# untitled.net
KiCad netlist of a schematic drawn in EAGLE
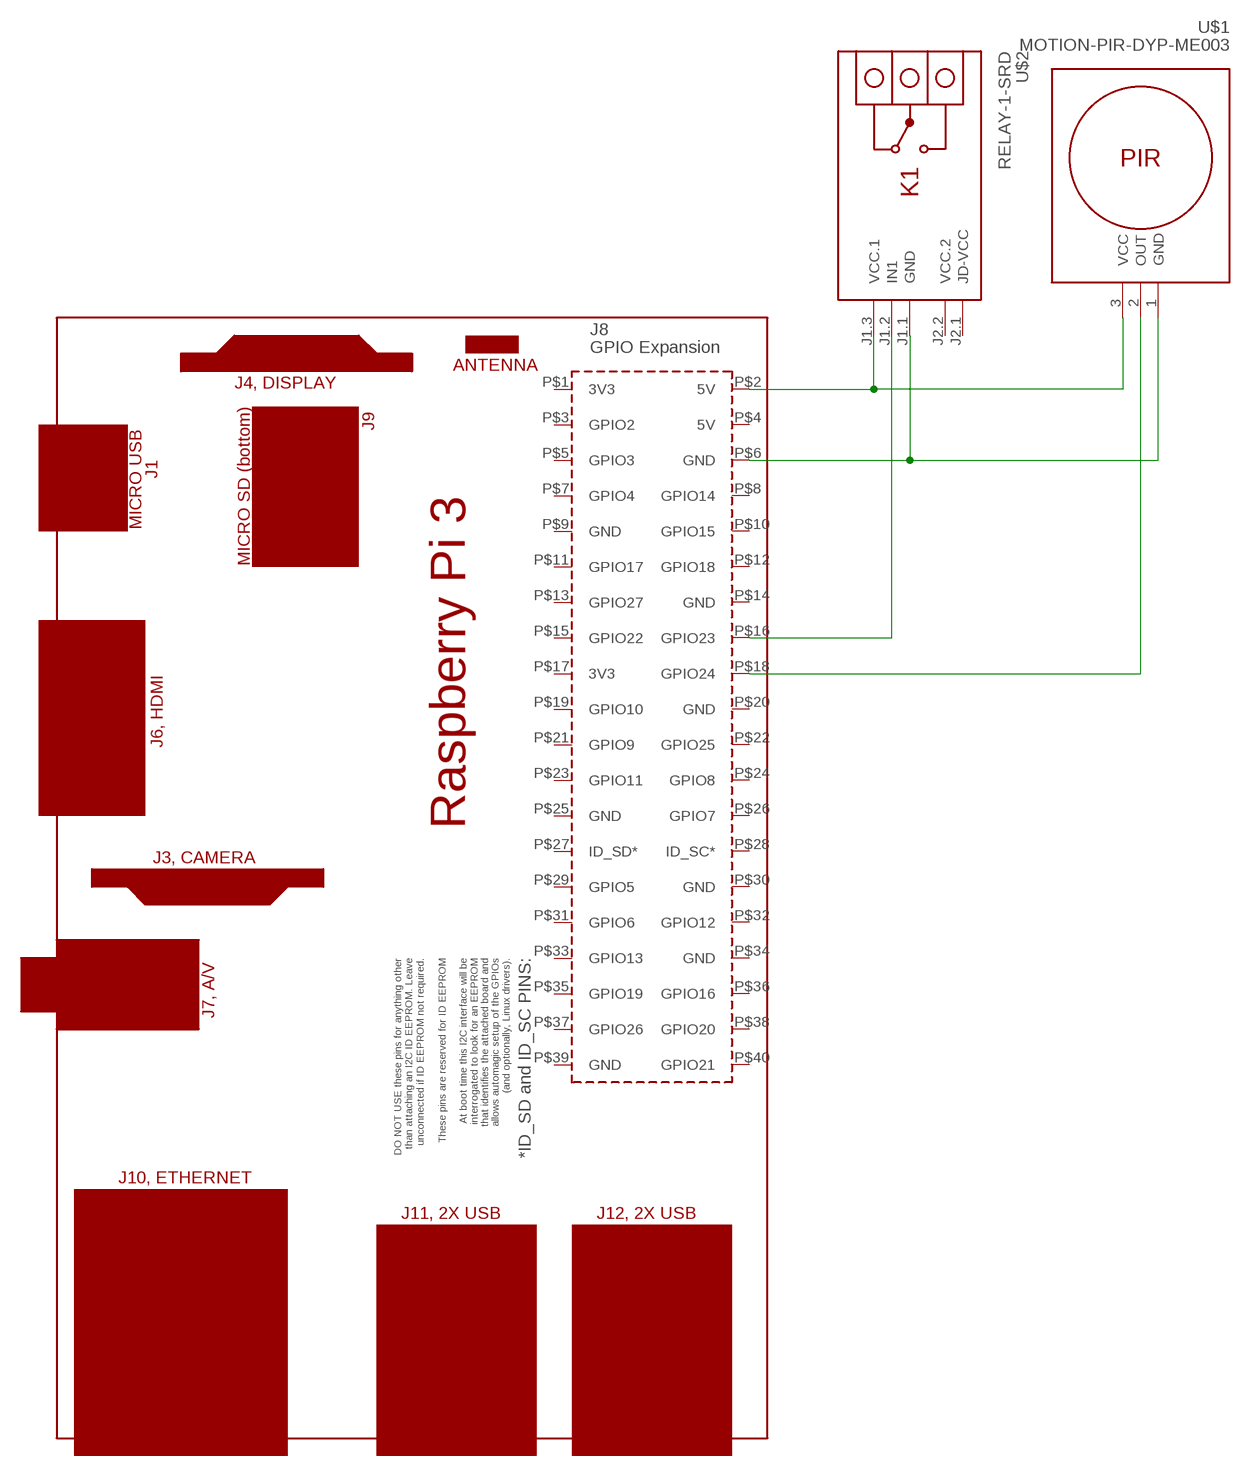
[diagram p0: schematic, sheet 1]

(export (version "E")
  (design (tool "Eeschema 10.0.6"))
  (components
    (comp (ref "PCB1")
      (value "RPI3RPI3")
      (footprint "eagle-import:RPI3")
      (libsource (lib "eagle-import") (part "RPI3RPI3"))
    )
    (comp (ref "U$1")
      (value "MOTION-PIR-DYP-ME003")
      (footprint "eagle-import:MOTION-PIR-DYP-ME003")
      (libsource (lib "eagle-import") (part "MOTION-PIR-DYP-ME003"))
    )
    (comp (ref "U$2")
      (value "RELAY-1-SRD")
      (footprint "eagle-import:RELAY-1-SRD")
      (libsource (lib "eagle-import") (part "RELAY-1-SRD"))
    )
  )
  (nets
    (net (code "1") (name "/VCC.2") (class "Default")
      (node (ref "U$2") (pin "J2.2") (pinfunction "VCC.2_J2.2") (pintype "power_in"))
    )
    (net (code "2") (name "Net-(PCB1-GPIO23)") (class "Default")
      (node (ref "PCB1") (pin "P$16") (pinfunction "GPIO23_P$16") (pintype "bidirectional"))
      (node (ref "U$2") (pin "J1.2") (pinfunction "IN1_J1.2") (pintype "bidirectional"))
    )
    (net (code "3") (name "Net-(PCB1-GPIO24)") (class "Default")
      (node (ref "PCB1") (pin "P$18") (pinfunction "GPIO24_P$18") (pintype "bidirectional"))
      (node (ref "U$1") (pin "2") (pinfunction "OUT_2") (pintype "output"))
    )
    (net (code "4") (name "Net-(U$1-GND)") (class "Default")
      (node (ref "PCB1") (pin "P$6") (pinfunction "GND_P$6") (pintype "bidirectional"))
      (node (ref "U$1") (pin "1") (pinfunction "GND_1") (pintype "power_in"))
      (node (ref "U$2") (pin "J1.1") (pinfunction "GND_J1.1") (pintype "power_in"))
    )
    (net (code "5") (name "Net-(U$1-VCC)") (class "Default")
      (node (ref "PCB1") (pin "P$2") (pinfunction "5V_P$2") (pintype "bidirectional"))
      (node (ref "U$1") (pin "3") (pinfunction "VCC_3") (pintype "power_in"))
      (node (ref "U$2") (pin "J1.3") (pinfunction "VCC.1_J1.3") (pintype "power_in"))
    )
    (net (code "6") (name "unconnected-(PCB1-3V3-PadP$1)") (class "Default")
      (node (ref "PCB1") (pin "P$1") (pinfunction "3V3_P$1") (pintype "bidirectional"))
    )
    (net (code "7") (name "unconnected-(PCB1-3V3-PadP$17)") (class "Default")
      (node (ref "PCB1") (pin "P$17") (pinfunction "3V3_P$17") (pintype "bidirectional"))
    )
    (net (code "8") (name "unconnected-(PCB1-5V-PadP$4)") (class "Default")
      (node (ref "PCB1") (pin "P$4") (pinfunction "5V_P$4") (pintype "bidirectional"))
    )
    (net (code "9") (name "unconnected-(PCB1-GND-PadP$9)") (class "Default")
      (node (ref "PCB1") (pin "P$9") (pinfunction "GND_P$9") (pintype "bidirectional"))
    )
    (net (code "10") (name "unconnected-(PCB1-GND-PadP$14)") (class "Default")
      (node (ref "PCB1") (pin "P$14") (pinfunction "GND_P$14") (pintype "bidirectional"))
    )
    (net (code "11") (name "unconnected-(PCB1-GND-PadP$20)") (class "Default")
      (node (ref "PCB1") (pin "P$20") (pinfunction "GND_P$20") (pintype "bidirectional"))
    )
    (net (code "12") (name "unconnected-(PCB1-GND-PadP$25)") (class "Default")
      (node (ref "PCB1") (pin "P$25") (pinfunction "GND_P$25") (pintype "bidirectional"))
    )
    (net (code "13") (name "unconnected-(PCB1-GND-PadP$30)") (class "Default")
      (node (ref "PCB1") (pin "P$30") (pinfunction "GND_P$30") (pintype "bidirectional"))
    )
    (net (code "14") (name "unconnected-(PCB1-GND-PadP$34)") (class "Default")
      (node (ref "PCB1") (pin "P$34") (pinfunction "GND_P$34") (pintype "bidirectional"))
    )
    (net (code "15") (name "unconnected-(PCB1-GND-PadP$39)") (class "Default")
      (node (ref "PCB1") (pin "P$39") (pinfunction "GND_P$39") (pintype "bidirectional"))
    )
    (net (code "16") (name "unconnected-(PCB1-GPIO2-PadP$3)") (class "Default")
      (node (ref "PCB1") (pin "P$3") (pinfunction "GPIO2_P$3") (pintype "bidirectional"))
    )
    (net (code "17") (name "unconnected-(PCB1-GPIO3-PadP$5)") (class "Default")
      (node (ref "PCB1") (pin "P$5") (pinfunction "GPIO3_P$5") (pintype "bidirectional"))
    )
    (net (code "18") (name "unconnected-(PCB1-GPIO4-PadP$7)") (class "Default")
      (node (ref "PCB1") (pin "P$7") (pinfunction "GPIO4_P$7") (pintype "bidirectional"))
    )
    (net (code "19") (name "unconnected-(PCB1-GPIO5-PadP$29)") (class "Default")
      (node (ref "PCB1") (pin "P$29") (pinfunction "GPIO5_P$29") (pintype "bidirectional"))
    )
    (net (code "20") (name "unconnected-(PCB1-GPIO6-PadP$31)") (class "Default")
      (node (ref "PCB1") (pin "P$31") (pinfunction "GPIO6_P$31") (pintype "bidirectional"))
    )
    (net (code "21") (name "unconnected-(PCB1-GPIO7-PadP$26)") (class "Default")
      (node (ref "PCB1") (pin "P$26") (pinfunction "GPIO7_P$26") (pintype "bidirectional"))
    )
    (net (code "22") (name "unconnected-(PCB1-GPIO8-PadP$24)") (class "Default")
      (node (ref "PCB1") (pin "P$24") (pinfunction "GPIO8_P$24") (pintype "bidirectional"))
    )
    (net (code "23") (name "unconnected-(PCB1-GPIO9-PadP$21)") (class "Default")
      (node (ref "PCB1") (pin "P$21") (pinfunction "GPIO9_P$21") (pintype "bidirectional"))
    )
    (net (code "24") (name "unconnected-(PCB1-GPIO10-PadP$19)") (class "Default")
      (node (ref "PCB1") (pin "P$19") (pinfunction "GPIO10_P$19") (pintype "bidirectional"))
    )
    (net (code "25") (name "unconnected-(PCB1-GPIO11-PadP$23)") (class "Default")
      (node (ref "PCB1") (pin "P$23") (pinfunction "GPIO11_P$23") (pintype "bidirectional"))
    )
    (net (code "26") (name "unconnected-(PCB1-GPIO12-PadP$32)") (class "Default")
      (node (ref "PCB1") (pin "P$32") (pinfunction "GPIO12_P$32") (pintype "bidirectional"))
    )
    (net (code "27") (name "unconnected-(PCB1-GPIO13-PadP$33)") (class "Default")
      (node (ref "PCB1") (pin "P$33") (pinfunction "GPIO13_P$33") (pintype "bidirectional"))
    )
    (net (code "28") (name "unconnected-(PCB1-GPIO14-PadP$8)") (class "Default")
      (node (ref "PCB1") (pin "P$8") (pinfunction "GPIO14_P$8") (pintype "bidirectional"))
    )
    (net (code "29") (name "unconnected-(PCB1-GPIO15-PadP$10)") (class "Default")
      (node (ref "PCB1") (pin "P$10") (pinfunction "GPIO15_P$10") (pintype "bidirectional"))
    )
    (net (code "30") (name "unconnected-(PCB1-GPIO16-PadP$36)") (class "Default")
      (node (ref "PCB1") (pin "P$36") (pinfunction "GPIO16_P$36") (pintype "bidirectional"))
    )
    (net (code "31") (name "unconnected-(PCB1-GPIO17-PadP$11)") (class "Default")
      (node (ref "PCB1") (pin "P$11") (pinfunction "GPIO17_P$11") (pintype "bidirectional"))
    )
    (net (code "32") (name "unconnected-(PCB1-GPIO18-PadP$12)") (class "Default")
      (node (ref "PCB1") (pin "P$12") (pinfunction "GPIO18_P$12") (pintype "bidirectional"))
    )
    (net (code "33") (name "unconnected-(PCB1-GPIO19-PadP$35)") (class "Default")
      (node (ref "PCB1") (pin "P$35") (pinfunction "GPIO19_P$35") (pintype "bidirectional"))
    )
    (net (code "34") (name "unconnected-(PCB1-GPIO20-PadP$38)") (class "Default")
      (node (ref "PCB1") (pin "P$38") (pinfunction "GPIO20_P$38") (pintype "bidirectional"))
    )
    (net (code "35") (name "unconnected-(PCB1-GPIO21-PadP$40)") (class "Default")
      (node (ref "PCB1") (pin "P$40") (pinfunction "GPIO21_P$40") (pintype "bidirectional"))
    )
    (net (code "36") (name "unconnected-(PCB1-GPIO22-PadP$15)") (class "Default")
      (node (ref "PCB1") (pin "P$15") (pinfunction "GPIO22_P$15") (pintype "bidirectional"))
    )
    (net (code "37") (name "unconnected-(PCB1-GPIO25-PadP$22)") (class "Default")
      (node (ref "PCB1") (pin "P$22") (pinfunction "GPIO25_P$22") (pintype "bidirectional"))
    )
    (net (code "38") (name "unconnected-(PCB1-GPIO26-PadP$37)") (class "Default")
      (node (ref "PCB1") (pin "P$37") (pinfunction "GPIO26_P$37") (pintype "bidirectional"))
    )
    (net (code "39") (name "unconnected-(PCB1-GPIO27-PadP$13)") (class "Default")
      (node (ref "PCB1") (pin "P$13") (pinfunction "GPIO27_P$13") (pintype "bidirectional"))
    )
    (net (code "40") (name "unconnected-(PCB1-ID_SC*-PadP$28)") (class "Default")
      (node (ref "PCB1") (pin "P$28") (pinfunction "ID_SC*_P$28") (pintype "bidirectional"))
    )
    (net (code "41") (name "unconnected-(PCB1-ID_SD*-PadP$27)") (class "Default")
      (node (ref "PCB1") (pin "P$27") (pinfunction "ID_SD*_P$27") (pintype "bidirectional"))
    )
    (net (code "42") (name "unconnected-(U$2-JD-VCC-PadJ2.1)") (class "Default")
      (node (ref "U$2") (pin "J2.1") (pinfunction "JD-VCC_J2.1") (pintype "bidirectional"))
    )
  )
)
